# Ldo_6V5_5V4.net
KiCad netlist of a schematic drawn in Altium Designer
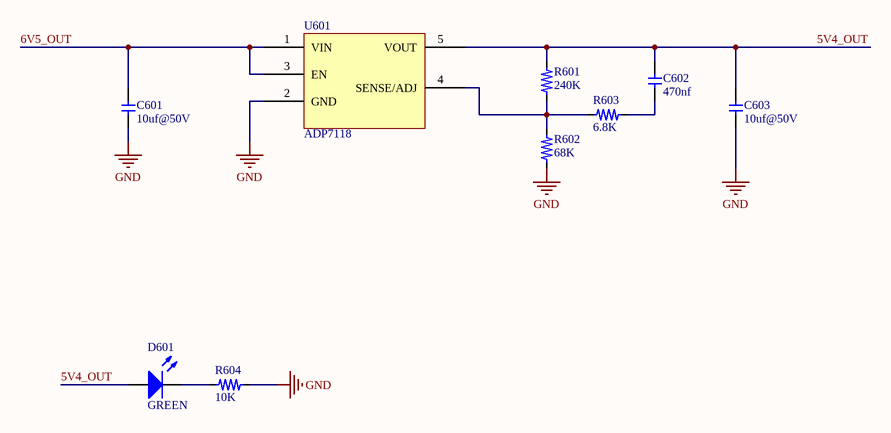
[diagram p0: Ldo.+6V5.+5V4.SchDoc]

(export (version "E")
  (design (tool "Eeschema 10.0.6"))
  (components
    (comp (ref "C601")
      (value "10uf@50V")
      (footprint "C1210")
      (fields (field (name "Comment") "Cap"))
      (libsource (lib "carrot_lib") (part "Cap"))
    )
    (comp (ref "C602")
      (value "470nf")
      (footprint "C0603")
      (fields (field (name "Comment") "Cap"))
      (libsource (lib "carrot_lib") (part "Cap"))
    )
    (comp (ref "C603")
      (value "10uf@50V")
      (footprint "C1210")
      (fields (field (name "Comment") "Cap"))
      (libsource (lib "carrot_lib") (part "Cap"))
    )
    (comp (ref "D601")
      (value "GREEN")
      (footprint "LED0603")
      (fields (field (name "Comment") "LED"))
      (libsource (lib "carrot_lib") (part "LED"))
    )
    (comp (ref "R601")
      (value "240K")
      (footprint "R0603")
      (description "电阻")
      (fields (field (name "Comment") "Res"))
      (libsource (lib "carrot_lib") (part "Res"))
    )
    (comp (ref "R602")
      (value "68K")
      (footprint "R0603")
      (description "电阻")
      (fields (field (name "Comment") "Res"))
      (libsource (lib "carrot_lib") (part "Res"))
    )
    (comp (ref "R603")
      (value "6.8K")
      (footprint "R0603")
      (description "电阻")
      (fields (field (name "Comment") "Res"))
      (libsource (lib "carrot_lib") (part "Res"))
    )
    (comp (ref "R604")
      (value "10K")
      (footprint "R0603")
      (description "电阻")
      (fields (field (name "Comment") "Res"))
      (libsource (lib "carrot_lib") (part "Res"))
    )
    (comp (ref "U601")
      (value "ADP7118")
      (footprint "ADP7118-TSOT5")
      (description "20 V, 200 mA, Low Noise,CMOS LDO Linear Regulator.")
      (libsource (lib "carrot_lib") (part "ADP7118AUJ"))
    )
  )
  (nets
    (net (code "1") (name "/5V4_OUT") (class "Default")
      (node (ref "C602") (pin "1") (pinfunction "1_1") (pintype "passive"))
      (node (ref "C603") (pin "2") (pinfunction "2_2") (pintype "passive"))
      (node (ref "D601") (pin "1") (pinfunction "A_1") (pintype "passive"))
      (node (ref "R601") (pin "2") (pinfunction "2_2") (pintype "passive"))
      (node (ref "U601") (pin "5") (pinfunction "VOUT_5") (pintype "passive"))
    )
    (net (code "2") (name "/6V5_OUT") (class "Default")
      (node (ref "C601") (pin "2") (pinfunction "2_2") (pintype "passive"))
      (node (ref "U601") (pin "1") (pinfunction "VIN_1") (pintype "passive"))
      (node (ref "U601") (pin "3") (pinfunction "EN_3") (pintype "passive"))
    )
    (net (code "3") (name "GND") (class "Default")
      (node (ref "C601") (pin "1") (pinfunction "1_1") (pintype "passive"))
      (node (ref "C603") (pin "1") (pinfunction "1_1") (pintype "passive"))
      (node (ref "R602") (pin "1") (pinfunction "1_1") (pintype "passive"))
      (node (ref "R604") (pin "1") (pinfunction "1_1") (pintype "passive"))
      (node (ref "U601") (pin "2") (pinfunction "GND_2") (pintype "passive"))
    )
    (net (code "4") (name "Net-(C602-Pad2)") (class "Default")
      (node (ref "C602") (pin "2") (pinfunction "2_2") (pintype "passive"))
      (node (ref "R603") (pin "1") (pinfunction "1_1") (pintype "passive"))
    )
    (net (code "5") (name "Net-(D601-K)") (class "Default")
      (node (ref "D601") (pin "2") (pinfunction "K_2") (pintype "passive"))
      (node (ref "R604") (pin "2") (pinfunction "2_2") (pintype "passive"))
    )
    (net (code "6") (name "Net-(U601-SENSE{slash}ADJ)") (class "Default")
      (node (ref "R601") (pin "1") (pinfunction "1_1") (pintype "passive"))
      (node (ref "R602") (pin "2") (pinfunction "2_2") (pintype "passive"))
      (node (ref "R603") (pin "2") (pinfunction "2_2") (pintype "passive"))
      (node (ref "U601") (pin "4") (pinfunction "SENSE/ADJ_4") (pintype "passive"))
    )
  )
)
